# 7_Key_Prototype.net
KiCad netlist of a schematic drawn in EAGLE
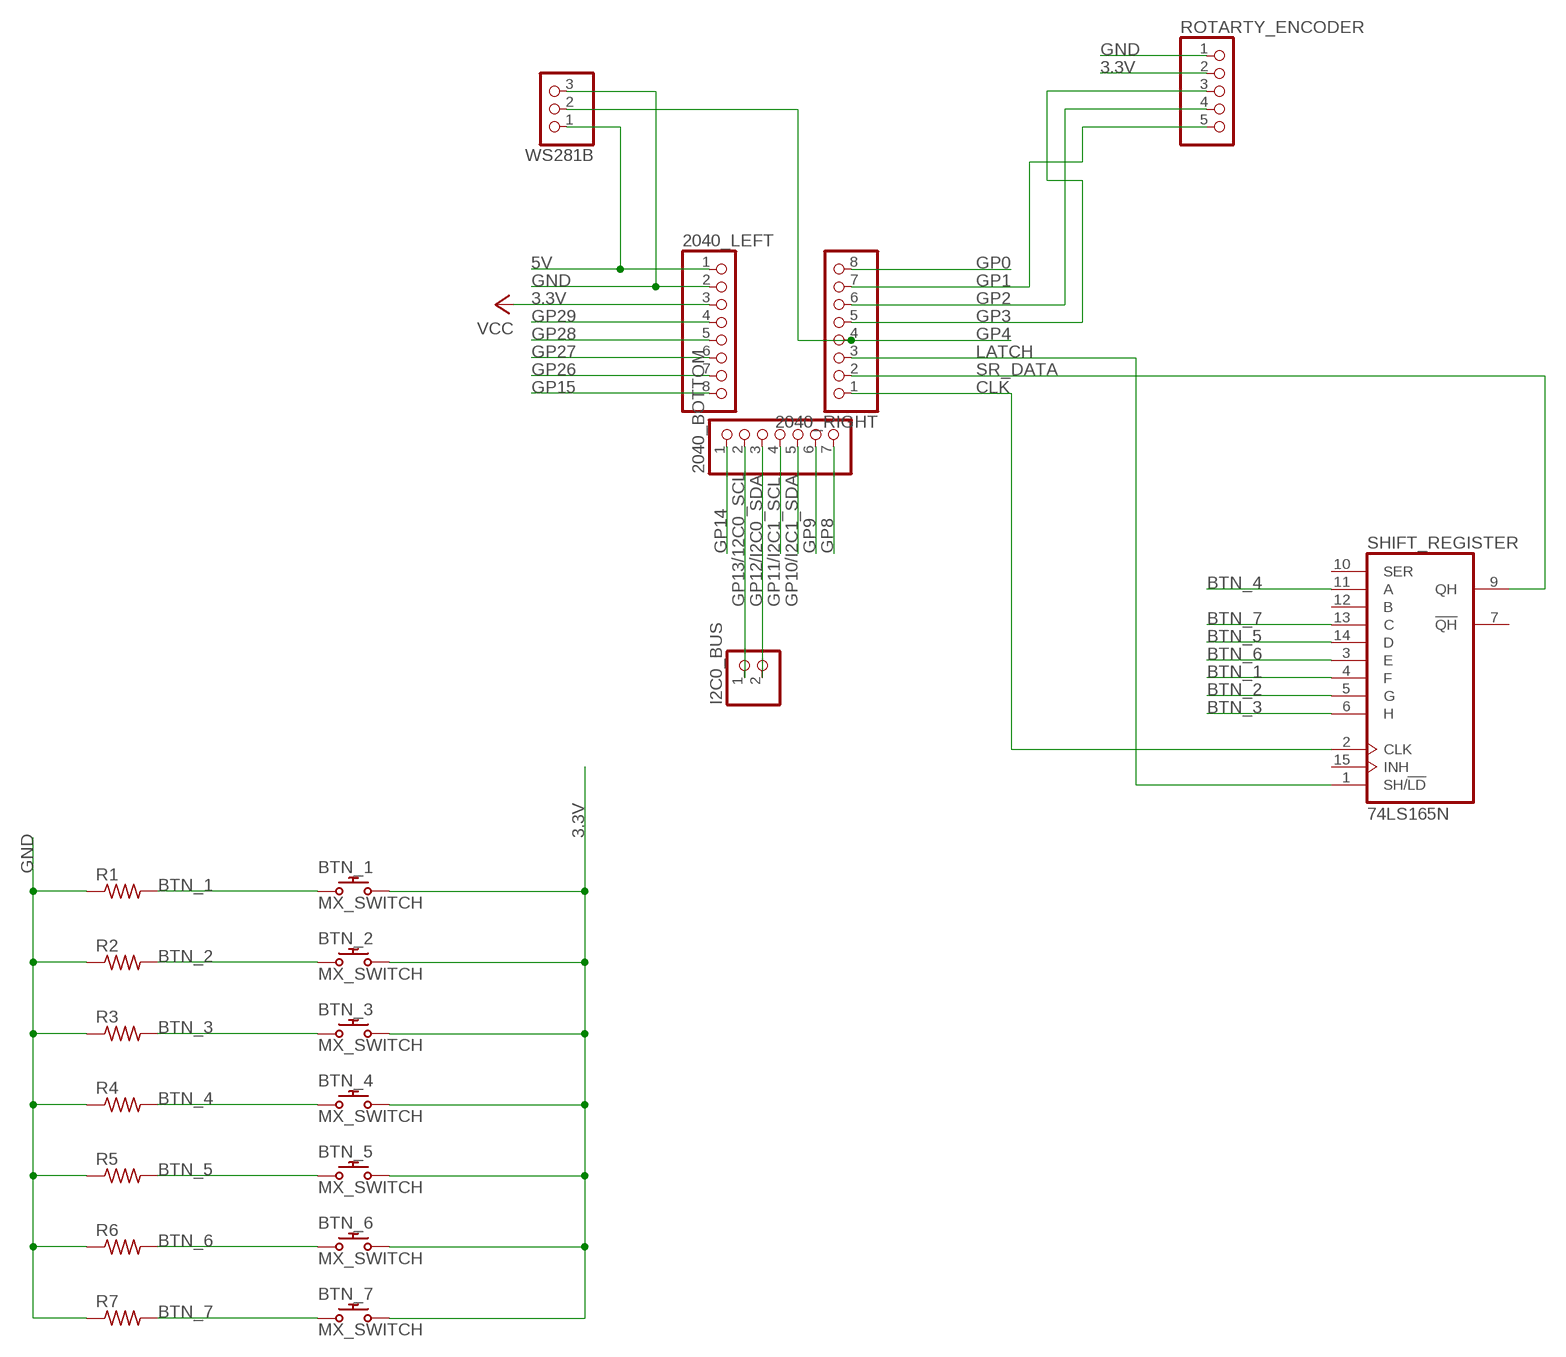
[diagram p0: schematic, sheet 1]

(export (version "E")
  (design (tool "Eeschema 10.0.6"))
  (components
    (comp (ref "2040_BOTTOM")
      (value "PINHD-1X7")
      (footprint "eagle-import:1X07")
      (libsource (lib "eagle-import") (part "PINHD-1X7"))
    )
    (comp (ref "2040_LEFT")
      (value "PINHD-1X8")
      (footprint "eagle-import:1X08")
      (libsource (lib "eagle-import") (part "PINHD-1X8"))
    )
    (comp (ref "2040_RIGHT")
      (value "PINHD-1X8")
      (footprint "eagle-import:1X08")
      (libsource (lib "eagle-import") (part "PINHD-1X8"))
    )
    (comp (ref "BTN_1")
      (value "MX_SWITCH")
      (footprint "eagle-import:MX_SWITCH")
      (libsource (lib "eagle-import") (part "MX_SWITCH"))
    )
    (comp (ref "BTN_2")
      (value "MX_SWITCH")
      (footprint "eagle-import:MX_SWITCH")
      (libsource (lib "eagle-import") (part "MX_SWITCH"))
    )
    (comp (ref "BTN_3")
      (value "MX_SWITCH")
      (footprint "eagle-import:MX_SWITCH")
      (libsource (lib "eagle-import") (part "MX_SWITCH"))
    )
    (comp (ref "BTN_4")
      (value "MX_SWITCH")
      (footprint "eagle-import:MX_SWITCH")
      (libsource (lib "eagle-import") (part "MX_SWITCH"))
    )
    (comp (ref "BTN_5")
      (value "MX_SWITCH")
      (footprint "eagle-import:MX_SWITCH")
      (libsource (lib "eagle-import") (part "MX_SWITCH"))
    )
    (comp (ref "BTN_6")
      (value "MX_SWITCH")
      (footprint "eagle-import:MX_SWITCH")
      (libsource (lib "eagle-import") (part "MX_SWITCH"))
    )
    (comp (ref "BTN_7")
      (value "MX_SWITCH")
      (footprint "eagle-import:MX_SWITCH")
      (libsource (lib "eagle-import") (part "MX_SWITCH"))
    )
    (comp (ref "I2C0_BUS")
      (value "PINHD-1X2")
      (footprint "eagle-import:1X02")
      (libsource (lib "eagle-import") (part "PINHD-1X2"))
    )
    (comp (ref "R1")
      (value "ADAFRUIT_R-US_R0805")
      (footprint "eagle-import:ADAFRUIT_R0805")
      (libsource (lib "eagle-import") (part "ADAFRUIT_R-US_R0805"))
    )
    (comp (ref "R2")
      (value "ADAFRUIT_R-US_R0805")
      (footprint "eagle-import:ADAFRUIT_R0805")
      (libsource (lib "eagle-import") (part "ADAFRUIT_R-US_R0805"))
    )
    (comp (ref "R3")
      (value "ADAFRUIT_R-US_R0805")
      (footprint "eagle-import:ADAFRUIT_R0805")
      (libsource (lib "eagle-import") (part "ADAFRUIT_R-US_R0805"))
    )
    (comp (ref "R4")
      (value "ADAFRUIT_R-US_R0805")
      (footprint "eagle-import:ADAFRUIT_R0805")
      (libsource (lib "eagle-import") (part "ADAFRUIT_R-US_R0805"))
    )
    (comp (ref "R5")
      (value "ADAFRUIT_R-US_R0805")
      (footprint "eagle-import:ADAFRUIT_R0805")
      (libsource (lib "eagle-import") (part "ADAFRUIT_R-US_R0805"))
    )
    (comp (ref "R6")
      (value "ADAFRUIT_R-US_R0805")
      (footprint "eagle-import:ADAFRUIT_R0805")
      (libsource (lib "eagle-import") (part "ADAFRUIT_R-US_R0805"))
    )
    (comp (ref "R7")
      (value "ADAFRUIT_R-US_R0805")
      (footprint "eagle-import:ADAFRUIT_R0805")
      (libsource (lib "eagle-import") (part "ADAFRUIT_R-US_R0805"))
    )
    (comp (ref "ROTARTY_ENCODER")
      (value "PINHD-1X5")
      (footprint "eagle-import:1X05")
      (libsource (lib "eagle-import") (part "PINHD-1X5"))
    )
    (comp (ref "SHIFT_REGISTER")
      (value "74LS165N")
      (footprint "eagle-import:DIL16")
      (libsource (lib "eagle-import") (part "74165NLS"))
    )
    (comp (ref "WS281B")
      (value "PINHD-1X3")
      (footprint "eagle-import:1X03")
      (libsource (lib "eagle-import") (part "PINHD-1X3"))
    )
  )
  (nets
    (net (code "1") (name "/5V") (class "Default")
      (node (ref "2040_LEFT") (pin "1") (pinfunction "1_1") (pintype "passive"))
      (node (ref "WS281B") (pin "1") (pinfunction "1_1") (pintype "passive"))
    )
    (net (code "2") (name "/BTN_1") (class "Default")
      (node (ref "BTN_1") (pin "S1") (pinfunction "1_S1") (pintype "passive"))
      (node (ref "R1") (pin "2") (pinfunction "2_2") (pintype "passive"))
      (node (ref "SHIFT_REGISTER") (pin "4") (pinfunction "F_4") (pintype "input"))
    )
    (net (code "3") (name "/BTN_2") (class "Default")
      (node (ref "BTN_2") (pin "S1") (pinfunction "1_S1") (pintype "passive"))
      (node (ref "R2") (pin "2") (pinfunction "2_2") (pintype "passive"))
      (node (ref "SHIFT_REGISTER") (pin "5") (pinfunction "G_5") (pintype "input"))
    )
    (net (code "4") (name "/BTN_3") (class "Default")
      (node (ref "BTN_3") (pin "S1") (pinfunction "1_S1") (pintype "passive"))
      (node (ref "R3") (pin "2") (pinfunction "2_2") (pintype "passive"))
      (node (ref "SHIFT_REGISTER") (pin "6") (pinfunction "H_6") (pintype "input"))
    )
    (net (code "5") (name "/BTN_4") (class "Default")
      (node (ref "BTN_4") (pin "S1") (pinfunction "1_S1") (pintype "passive"))
      (node (ref "R4") (pin "2") (pinfunction "2_2") (pintype "passive"))
      (node (ref "SHIFT_REGISTER") (pin "11") (pinfunction "A_11") (pintype "input"))
    )
    (net (code "6") (name "/BTN_5") (class "Default")
      (node (ref "BTN_5") (pin "S1") (pinfunction "1_S1") (pintype "passive"))
      (node (ref "R5") (pin "2") (pinfunction "2_2") (pintype "passive"))
      (node (ref "SHIFT_REGISTER") (pin "14") (pinfunction "D_14") (pintype "input"))
    )
    (net (code "7") (name "/BTN_6") (class "Default")
      (node (ref "BTN_6") (pin "S1") (pinfunction "1_S1") (pintype "passive"))
      (node (ref "R6") (pin "2") (pinfunction "2_2") (pintype "passive"))
      (node (ref "SHIFT_REGISTER") (pin "3") (pinfunction "E_3") (pintype "input"))
    )
    (net (code "8") (name "/BTN_7") (class "Default")
      (node (ref "BTN_7") (pin "S1") (pinfunction "1_S1") (pintype "passive"))
      (node (ref "R7") (pin "2") (pinfunction "2_2") (pintype "passive"))
      (node (ref "SHIFT_REGISTER") (pin "13") (pinfunction "C_13") (pintype "input"))
    )
    (net (code "9") (name "/CLK") (class "Default")
      (node (ref "2040_RIGHT") (pin "1") (pinfunction "1_1") (pintype "passive"))
      (node (ref "SHIFT_REGISTER") (pin "2") (pinfunction "CLK_2") (pintype "input"))
    )
    (net (code "10") (name "/GND") (class "Default")
      (node (ref "2040_LEFT") (pin "2") (pinfunction "2_2") (pintype "passive"))
      (node (ref "R1") (pin "1") (pinfunction "1_1") (pintype "passive"))
      (node (ref "R2") (pin "1") (pinfunction "1_1") (pintype "passive"))
      (node (ref "R3") (pin "1") (pinfunction "1_1") (pintype "passive"))
      (node (ref "R4") (pin "1") (pinfunction "1_1") (pintype "passive"))
      (node (ref "R5") (pin "1") (pinfunction "1_1") (pintype "passive"))
      (node (ref "R6") (pin "1") (pinfunction "1_1") (pintype "passive"))
      (node (ref "R7") (pin "1") (pinfunction "1_1") (pintype "passive"))
      (node (ref "ROTARTY_ENCODER") (pin "1") (pinfunction "1_1") (pintype "passive"))
      (node (ref "WS281B") (pin "3") (pinfunction "3_3") (pintype "passive"))
    )
    (net (code "11") (name "/GP0") (class "Default")
      (node (ref "2040_RIGHT") (pin "8") (pinfunction "8_8") (pintype "passive"))
    )
    (net (code "12") (name "/GP1") (class "Default")
      (node (ref "2040_RIGHT") (pin "7") (pinfunction "7_7") (pintype "passive"))
      (node (ref "ROTARTY_ENCODER") (pin "5") (pinfunction "5_5") (pintype "passive"))
    )
    (net (code "13") (name "/GP2") (class "Default")
      (node (ref "2040_RIGHT") (pin "6") (pinfunction "6_6") (pintype "passive"))
      (node (ref "ROTARTY_ENCODER") (pin "4") (pinfunction "4_4") (pintype "passive"))
    )
    (net (code "14") (name "/GP3") (class "Default")
      (node (ref "2040_RIGHT") (pin "5") (pinfunction "5_5") (pintype "passive"))
      (node (ref "ROTARTY_ENCODER") (pin "3") (pinfunction "3_3") (pintype "passive"))
    )
    (net (code "15") (name "/GP4") (class "Default")
      (node (ref "2040_RIGHT") (pin "4") (pinfunction "4_4") (pintype "passive"))
      (node (ref "WS281B") (pin "2") (pinfunction "2_2") (pintype "passive"))
    )
    (net (code "16") (name "/GP8") (class "Default")
      (node (ref "2040_BOTTOM") (pin "7") (pinfunction "7_7") (pintype "passive"))
    )
    (net (code "17") (name "/GP9") (class "Default")
      (node (ref "2040_BOTTOM") (pin "6") (pinfunction "6_6") (pintype "passive"))
    )
    (net (code "18") (name "/GP10{slash}I2C1_SDA") (class "Default")
      (node (ref "2040_BOTTOM") (pin "5") (pinfunction "5_5") (pintype "passive"))
    )
    (net (code "19") (name "/GP11{slash}I2C1_SCL") (class "Default")
      (node (ref "2040_BOTTOM") (pin "4") (pinfunction "4_4") (pintype "passive"))
    )
    (net (code "20") (name "/GP12{slash}I2C0_SDA") (class "Default")
      (node (ref "2040_BOTTOM") (pin "3") (pinfunction "3_3") (pintype "passive"))
      (node (ref "I2C0_BUS") (pin "2") (pinfunction "2_2") (pintype "passive"))
    )
    (net (code "21") (name "/GP13{slash}12C0_SCL") (class "Default")
      (node (ref "2040_BOTTOM") (pin "2") (pinfunction "2_2") (pintype "passive"))
      (node (ref "I2C0_BUS") (pin "1") (pinfunction "1_1") (pintype "passive"))
    )
    (net (code "22") (name "/GP14") (class "Default")
      (node (ref "2040_BOTTOM") (pin "1") (pinfunction "1_1") (pintype "passive"))
    )
    (net (code "23") (name "/GP15") (class "Default")
      (node (ref "2040_LEFT") (pin "8") (pinfunction "8_8") (pintype "passive"))
    )
    (net (code "24") (name "/GP26") (class "Default")
      (node (ref "2040_LEFT") (pin "7") (pinfunction "7_7") (pintype "passive"))
    )
    (net (code "25") (name "/GP27") (class "Default")
      (node (ref "2040_LEFT") (pin "6") (pinfunction "6_6") (pintype "passive"))
    )
    (net (code "26") (name "/GP28") (class "Default")
      (node (ref "2040_LEFT") (pin "5") (pinfunction "5_5") (pintype "passive"))
    )
    (net (code "27") (name "/GP29") (class "Default")
      (node (ref "2040_LEFT") (pin "4") (pinfunction "4_4") (pintype "passive"))
    )
    (net (code "28") (name "/LATCH") (class "Default")
      (node (ref "2040_RIGHT") (pin "3") (pinfunction "3_3") (pintype "passive"))
      (node (ref "SHIFT_REGISTER") (pin "1") (pinfunction "SH/~{LD}_1") (pintype "input"))
    )
    (net (code "29") (name "/SR_DATA") (class "Default")
      (node (ref "2040_RIGHT") (pin "2") (pinfunction "2_2") (pintype "passive"))
      (node (ref "SHIFT_REGISTER") (pin "9") (pinfunction "QH_9") (pintype "output"))
    )
    (net (code "30") (name "VCC") (class "Default")
      (node (ref "2040_LEFT") (pin "3") (pinfunction "3_3") (pintype "passive"))
      (node (ref "BTN_1") (pin "S2") (pinfunction "2_S2") (pintype "passive"))
      (node (ref "BTN_2") (pin "S2") (pinfunction "2_S2") (pintype "passive"))
      (node (ref "BTN_3") (pin "S2") (pinfunction "2_S2") (pintype "passive"))
      (node (ref "BTN_4") (pin "S2") (pinfunction "2_S2") (pintype "passive"))
      (node (ref "BTN_5") (pin "S2") (pinfunction "2_S2") (pintype "passive"))
      (node (ref "BTN_6") (pin "S2") (pinfunction "2_S2") (pintype "passive"))
      (node (ref "BTN_7") (pin "S2") (pinfunction "2_S2") (pintype "passive"))
      (node (ref "ROTARTY_ENCODER") (pin "2") (pinfunction "2_2") (pintype "passive"))
    )
    (net (code "31") (name "unconnected-(SHIFT_REGISTERA-B-Pad12)") (class "Default")
      (node (ref "SHIFT_REGISTER") (pin "12") (pinfunction "B_12") (pintype "input"))
    )
    (net (code "32") (name "unconnected-(SHIFT_REGISTERA-INH-Pad15)") (class "Default")
      (node (ref "SHIFT_REGISTER") (pin "15") (pinfunction "INH_15") (pintype "input"))
    )
    (net (code "33") (name "unconnected-(SHIFT_REGISTERA-SER-Pad10)") (class "Default")
      (node (ref "SHIFT_REGISTER") (pin "10") (pinfunction "SER_10") (pintype "input"))
    )
    (net (code "34") (name "unconnected-(SHIFT_REGISTERA-~{QH}-Pad7)") (class "Default")
      (node (ref "SHIFT_REGISTER") (pin "7") (pinfunction "~{QH}_7") (pintype "output"))
    )
  )
)
